# lp.net
KiCad netlist of a schematic drawn in EAGLE
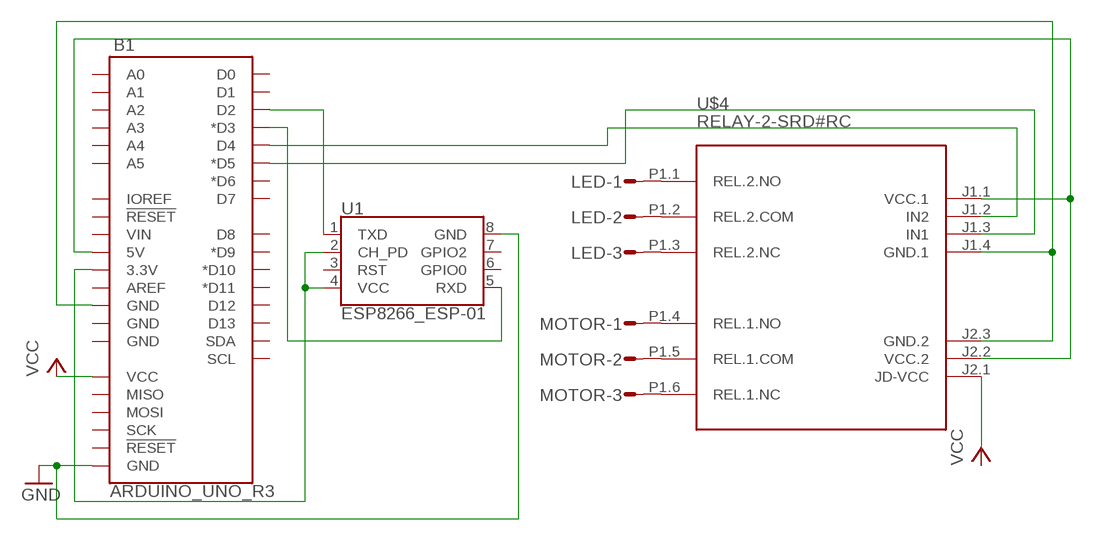
[diagram p0: schematic, sheet 1]

(export (version "E")
  (design (tool "Eeschema 10.0.6"))
  (components
    (comp (ref "B1")
      (value "ARDUINO_UNO_R3")
      (footprint "eagle-import:ARDUINO_R3")
      (libsource (lib "eagle-import") (part "ARDUINO_UNO_R3"))
    )
    (comp (ref "LED")
      (value "MT6-3Y")
      (footprint "eagle-import:MT6-3Y")
      (libsource (lib "eagle-import") (part "MT6-3Y"))
    )
    (comp (ref "MOTOR")
      (value "MT6-3Y")
      (footprint "eagle-import:MT6-3Y")
      (libsource (lib "eagle-import") (part "MT6-3Y"))
    )
    (comp (ref "U$4")
      (value "RELAY-2-SRD#RC")
      (footprint "eagle-import:RELAY-2-SRD#RC")
      (libsource (lib "eagle-import") (part "RELAY-2-SRD#RC"))
    )
    (comp (ref "U1")
      (value "ESP8266_ESP-01")
      (footprint "eagle-import:ESP8266_ESP-01")
      (libsource (lib "eagle-import") (part "ESP8266_ESP-01"))
    )
  )
  (nets
    (net (code "1") (name "GND") (class "Default")
      (node (ref "B1") (pin "GND@1") (pinfunction "GND_GND@1") (pintype "bidirectional"))
      (node (ref "U1") (pin "8") (pinfunction "GND_8") (pintype "bidirectional"))
    )
    (net (code "2") (name "Net-(B1-*D3)") (class "Default")
      (node (ref "B1") (pin "D3") (pinfunction "*D3_D3") (pintype "bidirectional"))
      (node (ref "U1") (pin "5") (pinfunction "RXD_5") (pintype "bidirectional"))
    )
    (net (code "3") (name "Net-(B1-*D5)") (class "Default")
      (node (ref "B1") (pin "D5") (pinfunction "*D5_D5") (pintype "bidirectional"))
      (node (ref "U$4") (pin "J1.3") (pinfunction "IN1_J1.3") (pintype "bidirectional"))
    )
    (net (code "4") (name "Net-(LEDA-S)") (class "Default")
      (node (ref "LED") (pin "1") (pinfunction "S_1") (pintype "passive"))
      (node (ref "U$4") (pin "P1.1") (pinfunction "REL.2.NO_P1.1") (pintype "bidirectional"))
    )
    (net (code "5") (name "Net-(LEDB-S)") (class "Default")
      (node (ref "LED") (pin "2") (pinfunction "S_2") (pintype "passive"))
      (node (ref "U$4") (pin "P1.2") (pinfunction "REL.2.COM_P1.2") (pintype "bidirectional"))
    )
    (net (code "6") (name "Net-(LEDC-S)") (class "Default")
      (node (ref "LED") (pin "3") (pinfunction "S_3") (pintype "passive"))
      (node (ref "U$4") (pin "P1.3") (pinfunction "REL.2.NC_P1.3") (pintype "bidirectional"))
    )
    (net (code "7") (name "Net-(MOTORA-S)") (class "Default")
      (node (ref "MOTOR") (pin "1") (pinfunction "S_1") (pintype "passive"))
      (node (ref "U$4") (pin "P1.4") (pinfunction "REL.1.NO_P1.4") (pintype "bidirectional"))
    )
    (net (code "8") (name "Net-(MOTORB-S)") (class "Default")
      (node (ref "MOTOR") (pin "2") (pinfunction "S_2") (pintype "passive"))
      (node (ref "U$4") (pin "P1.5") (pinfunction "REL.1.COM_P1.5") (pintype "bidirectional"))
    )
    (net (code "9") (name "Net-(MOTORC-S)") (class "Default")
      (node (ref "MOTOR") (pin "3") (pinfunction "S_3") (pintype "passive"))
      (node (ref "U$4") (pin "P1.6") (pinfunction "REL.1.NC_P1.6") (pintype "bidirectional"))
    )
    (net (code "10") (name "Net-(U$4-GND.1)") (class "Default")
      (node (ref "B1") (pin "GND@4") (pinfunction "GND_GND@4") (pintype "bidirectional"))
      (node (ref "U$4") (pin "J1.4") (pinfunction "GND.1_J1.4") (pintype "power_in"))
      (node (ref "U$4") (pin "J2.3") (pinfunction "GND.2_J2.3") (pintype "power_in"))
    )
    (net (code "11") (name "Net-(U$4-IN2)") (class "Default")
      (node (ref "B1") (pin "D4") (pinfunction "D4_D4") (pintype "bidirectional"))
      (node (ref "U$4") (pin "J1.2") (pinfunction "IN2_J1.2") (pintype "bidirectional"))
    )
    (net (code "12") (name "Net-(U$4-VCC.1)") (class "Default")
      (node (ref "B1") (pin "5V") (pinfunction "5V_5V") (pintype "bidirectional"))
      (node (ref "U$4") (pin "J1.1") (pinfunction "VCC.1_J1.1") (pintype "power_in"))
      (node (ref "U$4") (pin "J2.2") (pinfunction "VCC.2_J2.2") (pintype "power_in"))
    )
    (net (code "13") (name "Net-(U1-CH_PD)") (class "Default")
      (node (ref "B1") (pin "3.3V") (pinfunction "3.3V_3.3V") (pintype "bidirectional"))
      (node (ref "U1") (pin "2") (pinfunction "CH_PD_2") (pintype "bidirectional"))
      (node (ref "U1") (pin "4") (pinfunction "VCC_4") (pintype "bidirectional"))
    )
    (net (code "14") (name "Net-(U1-TXD)") (class "Default")
      (node (ref "B1") (pin "D2") (pinfunction "D2_D2") (pintype "bidirectional"))
      (node (ref "U1") (pin "1") (pinfunction "TXD_1") (pintype "bidirectional"))
    )
    (net (code "15") (name "VCC") (class "Default")
      (node (ref "B1") (pin "VCC") (pinfunction "VCC_VCC") (pintype "bidirectional"))
      (node (ref "U$4") (pin "J2.1") (pinfunction "JD-VCC_J2.1") (pintype "bidirectional"))
    )
    (net (code "16") (name "unconnected-(B1-*D6-PadD6)") (class "Default")
      (node (ref "B1") (pin "D6") (pinfunction "*D6_D6") (pintype "bidirectional"))
    )
    (net (code "17") (name "unconnected-(B1-*D9-PadD9)") (class "Default")
      (node (ref "B1") (pin "D9") (pinfunction "*D9_D9") (pintype "bidirectional"))
    )
    (net (code "18") (name "unconnected-(B1-*D10-PadD10)") (class "Default")
      (node (ref "B1") (pin "D10") (pinfunction "*D10_D10") (pintype "bidirectional"))
    )
    (net (code "19") (name "unconnected-(B1-*D11-PadD11)") (class "Default")
      (node (ref "B1") (pin "D11") (pinfunction "*D11_D11") (pintype "bidirectional"))
    )
    (net (code "20") (name "unconnected-(B1-GND-PadGND@2)") (class "Default")
      (node (ref "B1") (pin "GND@2") (pinfunction "GND_GND@2") (pintype "bidirectional"))
    )
    (net (code "21") (name "unconnected-(B1-GND-PadGND@3)") (class "Default")
      (node (ref "B1") (pin "GND@3") (pinfunction "GND_GND@3") (pintype "bidirectional"))
    )
    (net (code "22") (name "unconnected-(B1-PadA0)") (class "Default")
      (node (ref "B1") (pin "A0") (pinfunction "A0_A0") (pintype "bidirectional"))
    )
    (net (code "23") (name "unconnected-(B1-PadA1)") (class "Default")
      (node (ref "B1") (pin "A1") (pinfunction "A1_A1") (pintype "bidirectional"))
    )
    (net (code "24") (name "unconnected-(B1-PadA2)") (class "Default")
      (node (ref "B1") (pin "A2") (pinfunction "A2_A2") (pintype "bidirectional"))
    )
    (net (code "25") (name "unconnected-(B1-PadA3)") (class "Default")
      (node (ref "B1") (pin "A3") (pinfunction "A3_A3") (pintype "bidirectional"))
    )
    (net (code "26") (name "unconnected-(B1-PadA4)") (class "Default")
      (node (ref "B1") (pin "A4") (pinfunction "A4_A4") (pintype "bidirectional"))
    )
    (net (code "27") (name "unconnected-(B1-PadA5)") (class "Default")
      (node (ref "B1") (pin "A5") (pinfunction "A5_A5") (pintype "bidirectional"))
    )
    (net (code "28") (name "unconnected-(B1-PadAREF)") (class "Default")
      (node (ref "B1") (pin "AREF") (pinfunction "AREF_AREF") (pintype "bidirectional"))
    )
    (net (code "29") (name "unconnected-(B1-PadD0)") (class "Default")
      (node (ref "B1") (pin "D0") (pinfunction "D0_D0") (pintype "bidirectional"))
    )
    (net (code "30") (name "unconnected-(B1-PadD1)") (class "Default")
      (node (ref "B1") (pin "D1") (pinfunction "D1_D1") (pintype "bidirectional"))
    )
    (net (code "31") (name "unconnected-(B1-PadD7)") (class "Default")
      (node (ref "B1") (pin "D7") (pinfunction "D7_D7") (pintype "bidirectional"))
    )
    (net (code "32") (name "unconnected-(B1-PadD8)") (class "Default")
      (node (ref "B1") (pin "D8") (pinfunction "D8_D8") (pintype "bidirectional"))
    )
    (net (code "33") (name "unconnected-(B1-PadD12)") (class "Default")
      (node (ref "B1") (pin "D12") (pinfunction "D12_D12") (pintype "bidirectional"))
    )
    (net (code "34") (name "unconnected-(B1-PadD13)") (class "Default")
      (node (ref "B1") (pin "D13") (pinfunction "D13_D13") (pintype "bidirectional"))
    )
    (net (code "35") (name "unconnected-(B1-PadIOREF)") (class "Default")
      (node (ref "B1") (pin "IOREF") (pinfunction "IOREF_IOREF") (pintype "bidirectional"))
    )
    (net (code "36") (name "unconnected-(B1-PadMISO)") (class "Default")
      (node (ref "B1") (pin "MISO") (pinfunction "MISO_MISO") (pintype "bidirectional"))
    )
    (net (code "37") (name "unconnected-(B1-PadMOSI)") (class "Default")
      (node (ref "B1") (pin "MOSI") (pinfunction "MOSI_MOSI") (pintype "bidirectional"))
    )
    (net (code "38") (name "unconnected-(B1-PadSCK)") (class "Default")
      (node (ref "B1") (pin "SCK") (pinfunction "SCK_SCK") (pintype "bidirectional"))
    )
    (net (code "39") (name "unconnected-(B1-PadSCL)") (class "Default")
      (node (ref "B1") (pin "SCL") (pinfunction "SCL_SCL") (pintype "bidirectional"))
    )
    (net (code "40") (name "unconnected-(B1-PadSDA)") (class "Default")
      (node (ref "B1") (pin "SDA") (pinfunction "SDA_SDA") (pintype "bidirectional"))
    )
    (net (code "41") (name "unconnected-(B1-PadVIN)") (class "Default")
      (node (ref "B1") (pin "VIN") (pinfunction "VIN_VIN") (pintype "bidirectional"))
    )
    (net (code "42") (name "unconnected-(B1-~{RESET}-PadRESET@1)") (class "Default")
      (node (ref "B1") (pin "RESET@1") (pinfunction "~{RESET}_RESET@1") (pintype "bidirectional"))
    )
    (net (code "43") (name "unconnected-(B1-~{RESET}-PadRESET@2)") (class "Default")
      (node (ref "B1") (pin "RESET@2") (pinfunction "~{RESET}_RESET@2") (pintype "bidirectional"))
    )
    (net (code "44") (name "unconnected-(U1-GPIO0-Pad6)") (class "Default")
      (node (ref "U1") (pin "6") (pinfunction "GPIO0_6") (pintype "bidirectional"))
    )
    (net (code "45") (name "unconnected-(U1-GPIO2-Pad7)") (class "Default")
      (node (ref "U1") (pin "7") (pinfunction "GPIO2_7") (pintype "bidirectional"))
    )
    (net (code "46") (name "unconnected-(U1-RST-Pad3)") (class "Default")
      (node (ref "U1") (pin "3") (pinfunction "RST_3") (pintype "bidirectional"))
    )
  )
)
